# mb1045.net
KiCad netlist of a schematic drawn in Altium Designer
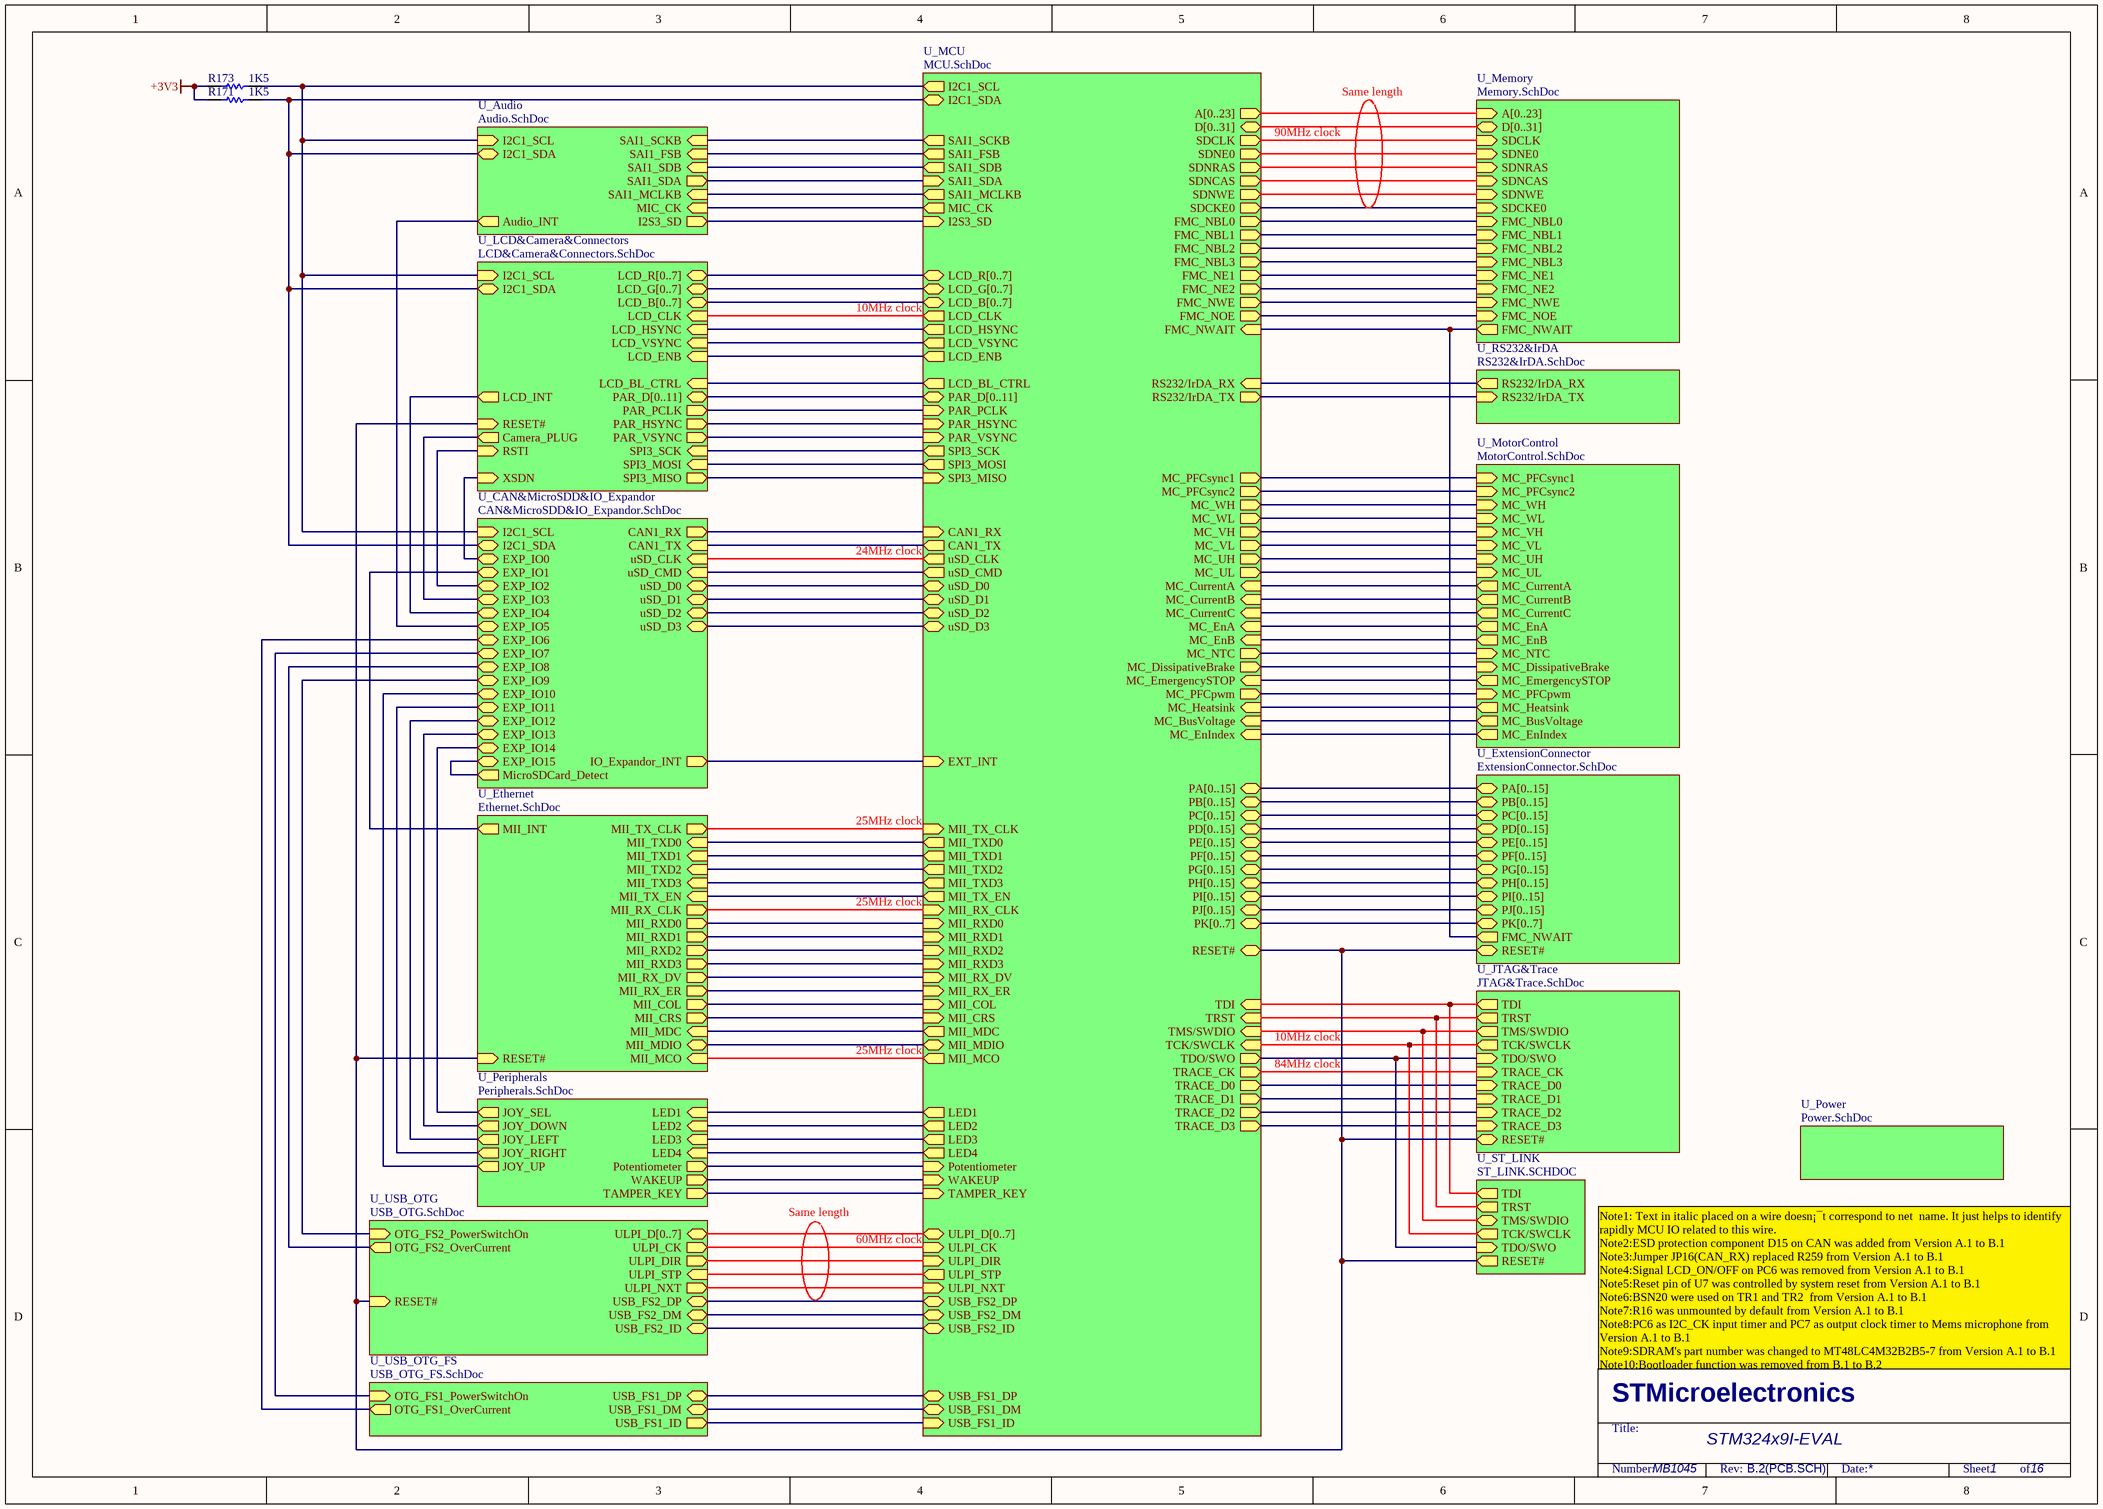
[diagram p0: mb1045.SchDoc]

(export (version "E")
  (design (tool "Eeschema 10.0.6"))
  (components
    (comp (ref "R171")
      (value "1K5")
      (footprint "0603R")
      (description "Resistor")
      (fields (field (name "PUBLISHER") "Altium Limited"))
      (libsource (lib "Miscellaneous Devices") (part "Res1"))
    )
    (comp (ref "R173")
      (value "1K5")
      (footprint "0603R")
      (description "Resistor")
      (fields (field (name "PUBLISHER") "Altium Limited"))
      (libsource (lib "Miscellaneous Devices") (part "Res1"))
    )
  )
  (nets
    (net (code "1") (name "+3V3") (class "Default")
      (node (ref "R171") (pin "1") (pinfunction "1_1") (pintype "passive"))
      (node (ref "R173") (pin "1") (pinfunction "1_1") (pintype "passive"))
    )
    (net (code "21") (name "/I2C1_SCL") (class "Default")
      (node (ref "R173") (pin "2") (pinfunction "2_2") (pintype "passive"))
    )
    (net (code "22") (name "/I2C1_SDA") (class "Default")
      (node (ref "R171") (pin "2") (pinfunction "2_2") (pintype "passive"))
    )
  )
)
